# USB_Interface.net
KiCad netlist of a schematic drawn in Altium Designer
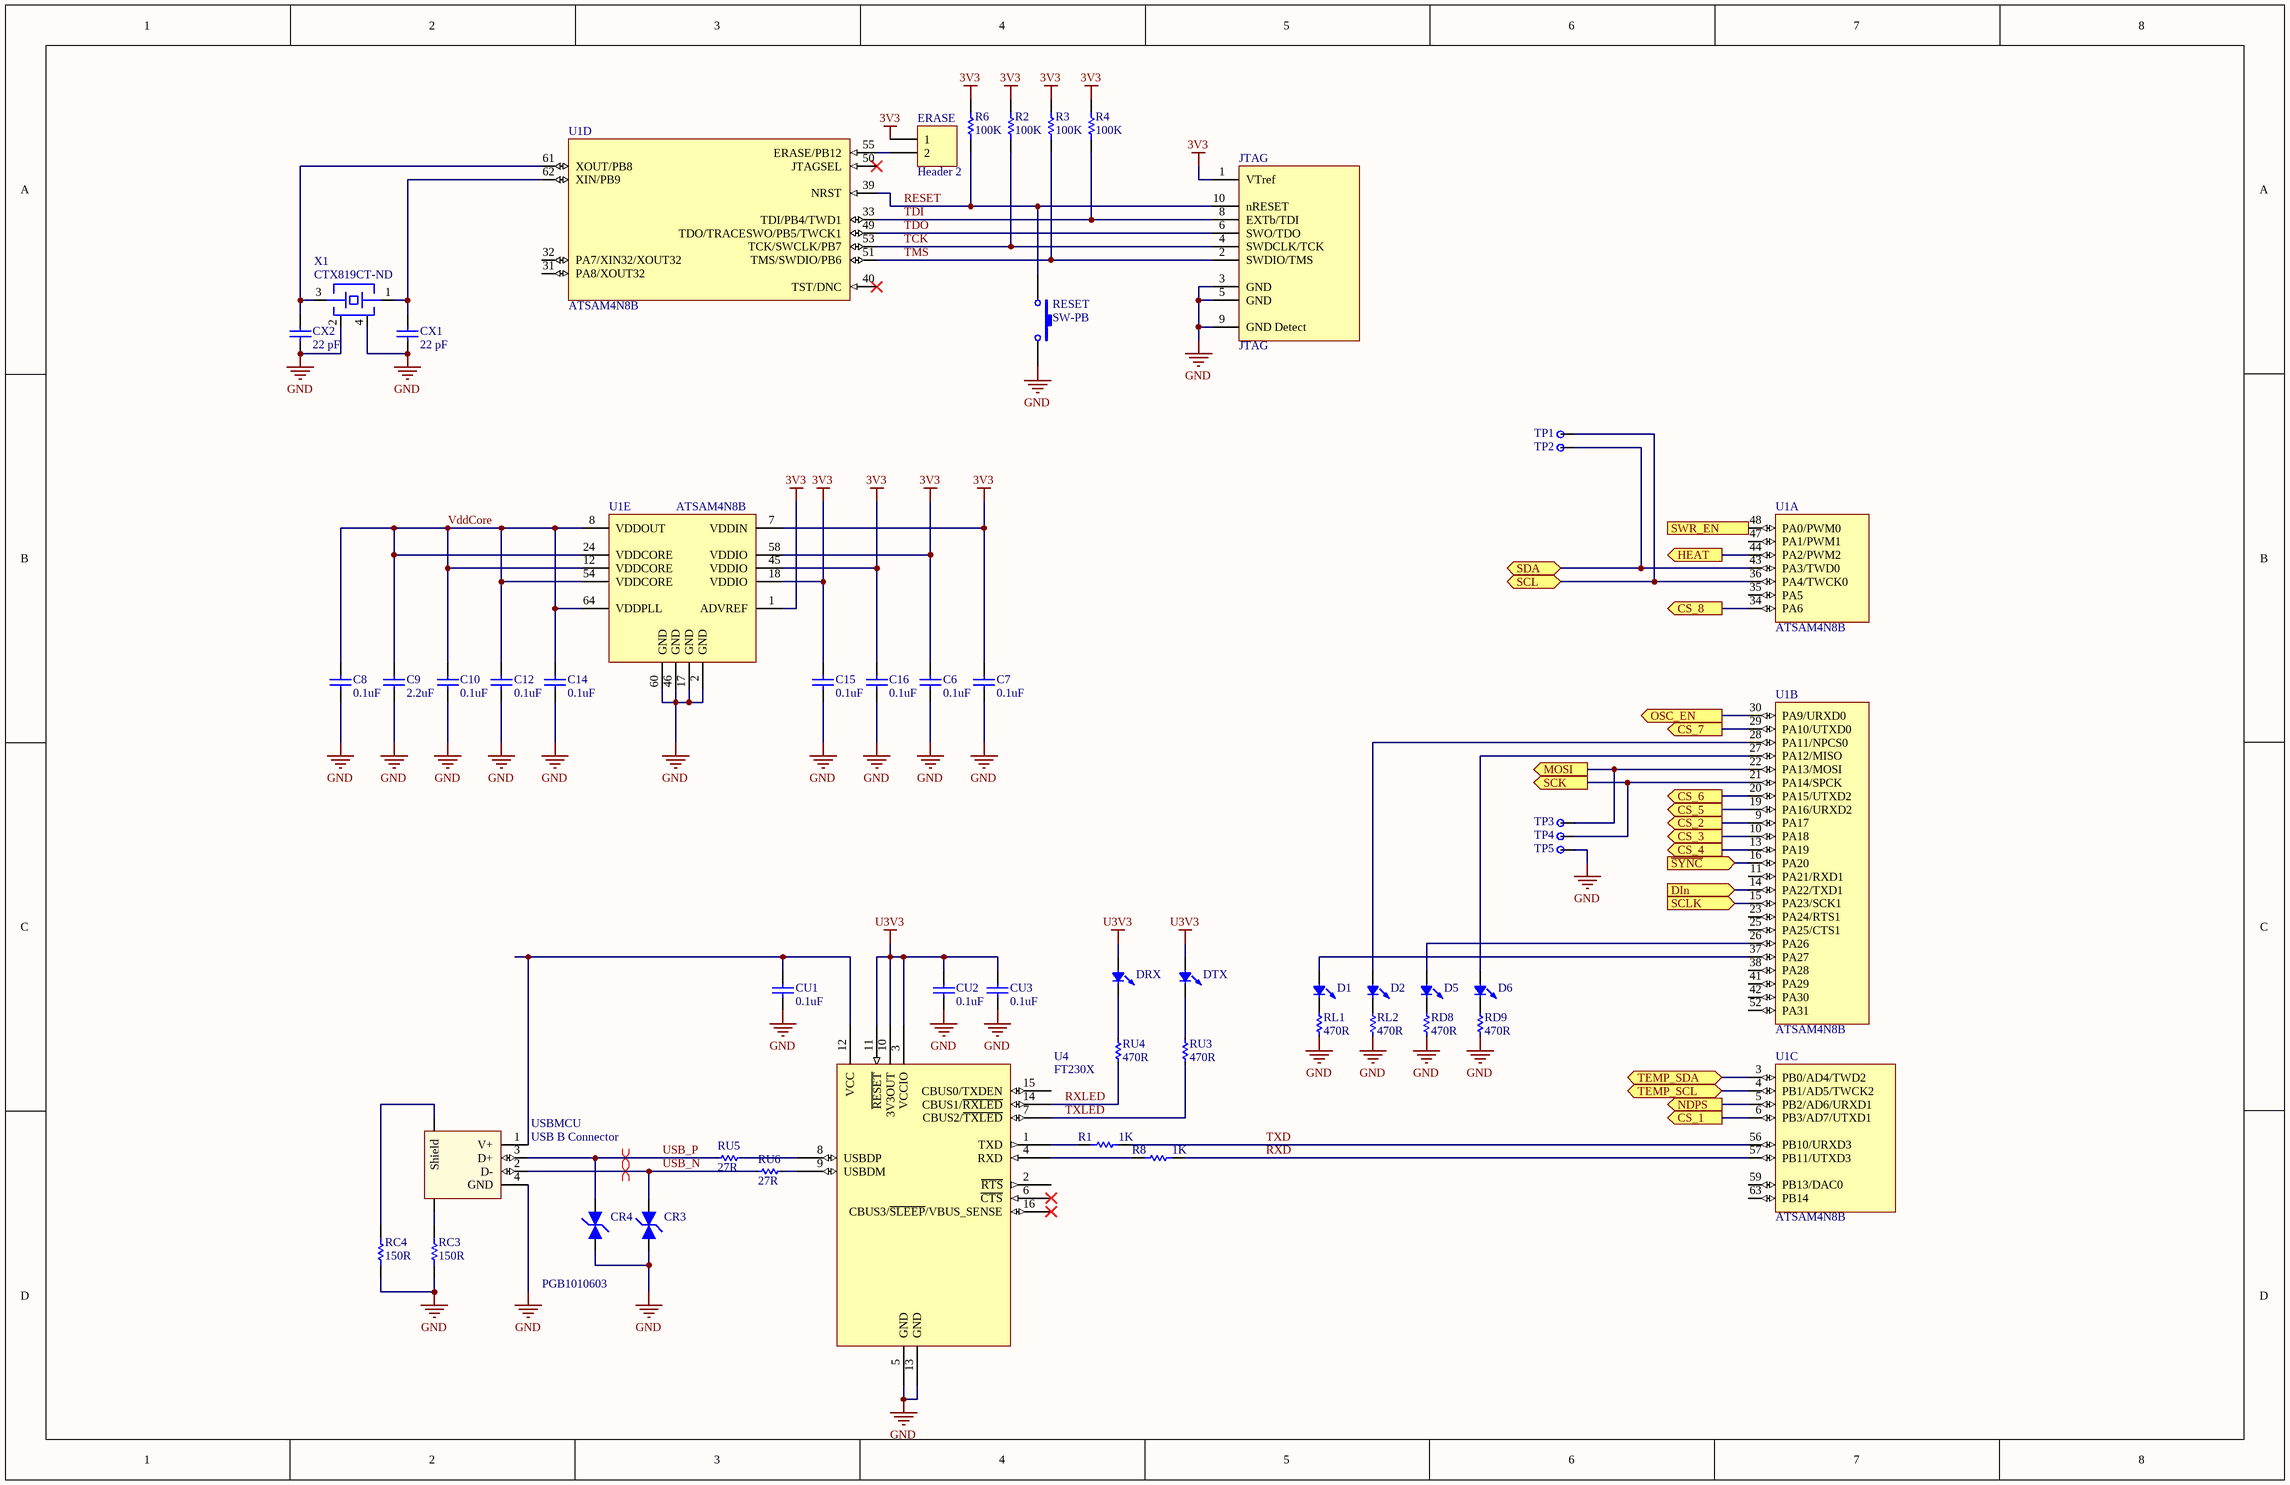
[diagram p0: USB Interface.SchDoc]

(export (version "E")
  (design (tool "Eeschema 10.0.6"))
  (components
    (comp (ref "C6")
      (value "0.1uF")
      (footprint "0603C")
      (description "Capacitor (Semiconductor SIM Model)")
      (fields (field (name "Comment") "Cap Semi") (field (name "PUBLISHER") "Altium Limited"))
      (libsource (lib "Miscellaneous Devices") (part "Cap Semi"))
    )
    (comp (ref "C7")
      (value "0.1uF")
      (footprint "0603C")
      (description "Capacitor (Semiconductor SIM Model)")
      (fields (field (name "Comment") "Cap Semi") (field (name "PUBLISHER") "Altium Limited"))
      (libsource (lib "Miscellaneous Devices") (part "Cap Semi"))
    )
    (comp (ref "C8")
      (value "0.1uF")
      (footprint "0603C")
      (description "Capacitor (Semiconductor SIM Model)")
      (fields (field (name "Comment") "Cap Semi") (field (name "PUBLISHER") "Altium Limited"))
      (libsource (lib "Miscellaneous Devices") (part "Cap Semi"))
    )
    (comp (ref "C9")
      (value "2.2uF")
      (footprint "1206C")
      (description "Capacitor (Semiconductor SIM Model)")
      (fields (field (name "Comment") "Cap Semi") (field (name "PUBLISHER") "Altium Limited"))
      (libsource (lib "Miscellaneous Devices") (part "Cap Semi"))
    )
    (comp (ref "C10")
      (value "0.1uF")
      (footprint "0603C")
      (description "Capacitor (Semiconductor SIM Model)")
      (fields (field (name "Comment") "Cap Semi") (field (name "PUBLISHER") "Altium Limited"))
      (libsource (lib "Miscellaneous Devices") (part "Cap Semi"))
    )
    (comp (ref "C12")
      (value "0.1uF")
      (footprint "0603C")
      (description "Capacitor (Semiconductor SIM Model)")
      (fields (field (name "Comment") "Cap Semi") (field (name "PUBLISHER") "Altium Limited"))
      (libsource (lib "Miscellaneous Devices") (part "Cap Semi"))
    )
    (comp (ref "C14")
      (value "0.1uF")
      (footprint "0603C")
      (description "Capacitor (Semiconductor SIM Model)")
      (fields (field (name "Comment") "Cap Semi") (field (name "PUBLISHER") "Altium Limited"))
      (libsource (lib "Miscellaneous Devices") (part "Cap Semi"))
    )
    (comp (ref "C15")
      (value "0.1uF")
      (footprint "0603C")
      (description "Capacitor (Semiconductor SIM Model)")
      (fields (field (name "Comment") "Cap Semi") (field (name "PUBLISHER") "Altium Limited"))
      (libsource (lib "Miscellaneous Devices") (part "Cap Semi"))
    )
    (comp (ref "C16")
      (value "0.1uF")
      (footprint "0603C")
      (description "Capacitor (Semiconductor SIM Model)")
      (fields (field (name "Comment") "Cap Semi") (field (name "PUBLISHER") "Altium Limited"))
      (libsource (lib "Miscellaneous Devices") (part "Cap Semi"))
    )
    (comp (ref "CR3")
      (value "PGB1010603")
      (footprint "0603PG")
      (description "PulseGuard® Lead-Free 0603 Surface Mount Polymeric ESD Suppressors")
      (libsource (lib "DAQ System") (part "PGB1010603"))
    )
    (comp (ref "CR4")
      (value "PGB1010603")
      (footprint "0603PG")
      (description "PulseGuard® Lead-Free 0603 Surface Mount Polymeric ESD Suppressors")
      (libsource (lib "DAQ System") (part "PGB1010603"))
    )
    (comp (ref "CU1")
      (value "0.1uF")
      (footprint "0603C")
      (description "Capacitor (Semiconductor SIM Model)")
      (fields (field (name "Comment") "Cap Semi") (field (name "PUBLISHER") "Altium Limited"))
      (libsource (lib "Miscellaneous Devices") (part "Cap Semi"))
    )
    (comp (ref "CU2")
      (value "0.1uF")
      (footprint "0603C")
      (description "Capacitor (Semiconductor SIM Model)")
      (fields (field (name "Comment") "Cap Semi") (field (name "PUBLISHER") "Altium Limited"))
      (libsource (lib "Miscellaneous Devices") (part "Cap Semi"))
    )
    (comp (ref "CU3")
      (value "0.1uF")
      (footprint "0603C")
      (description "Capacitor (Semiconductor SIM Model)")
      (fields (field (name "Comment") "Cap Semi") (field (name "PUBLISHER") "Altium Limited"))
      (libsource (lib "Miscellaneous Devices") (part "Cap Semi"))
    )
    (comp (ref "CX1")
      (value "22 pF")
      (footprint "0603C")
      (description "Capacitor (Semiconductor SIM Model)")
      (fields (field (name "Comment") "Cap Semi") (field (name "PUBLISHER") "Altium Limited"))
      (libsource (lib "Miscellaneous Devices") (part "Cap Semi"))
    )
    (comp (ref "CX2")
      (value "22 pF")
      (footprint "0603C")
      (description "Capacitor (Semiconductor SIM Model)")
      (fields (field (name "Comment") "Cap Semi") (field (name "PUBLISHER") "Altium Limited"))
      (libsource (lib "Miscellaneous Devices") (part "Cap Semi"))
    )
    (comp (ref "D1")
      (value "LED0")
      (footprint "0603 SMT LED")
      (description "T 1 3/4 LED")
      (fields (field (name "PUBLISHER") "Altium Limited"))
      (libsource (lib "Miscellaneous Devices") (part "LED0"))
    )
    (comp (ref "D2")
      (value "LED0")
      (footprint "0603 SMT LED")
      (description "T 1 3/4 LED")
      (fields (field (name "PUBLISHER") "Altium Limited"))
      (libsource (lib "Miscellaneous Devices") (part "LED0"))
    )
    (comp (ref "D5")
      (value "LED0")
      (footprint "0603 SMT LED")
      (description "T 1 3/4 LED")
      (fields (field (name "PUBLISHER") "Altium Limited"))
      (libsource (lib "Miscellaneous Devices") (part "LED0"))
    )
    (comp (ref "D6")
      (value "LED0")
      (footprint "0603 SMT LED")
      (description "T 1 3/4 LED")
      (fields (field (name "PUBLISHER") "Altium Limited"))
      (libsource (lib "Miscellaneous Devices") (part "LED0"))
    )
    (comp (ref "DRX")
      (value "LED0")
      (footprint "0603 SMT LED")
      (description "T 1 3/4 LED")
      (fields (field (name "PUBLISHER") "Altium Limited"))
      (libsource (lib "Miscellaneous Devices") (part "LED0"))
    )
    (comp (ref "DTX")
      (value "LED0")
      (footprint "0603 SMT LED")
      (description "T 1 3/4 LED")
      (fields (field (name "PUBLISHER") "Altium Limited"))
      (libsource (lib "Miscellaneous Devices") (part "LED0"))
    )
    (comp (ref "ERASE")
      (value "Header 2")
      (footprint "HDR1X2")
      (description "Header, 2-Pin")
      (fields (field (name "PUBLISHER") "Altium Limited"))
      (libsource (lib "Miscellaneous Connectors") (part "Header 2"))
    )
    (comp (ref "JTAG")
      (value "JTAG")
      (footprint "MHDR2X5 - Shrouded")
      (description "ARM 10-Pin JTAG Interface")
      (libsource (lib "Connectors") (part "ARM JTAG-10"))
    )
    (comp (ref "R1")
      (value "1K")
      (footprint "0603R")
      (description "Semiconductor Resistor")
      (fields (field (name "Comment") "Res Semi") (field (name "PUBLISHER") "Altium Limited"))
      (libsource (lib "Miscellaneous Devices") (part "Res Semi"))
    )
    (comp (ref "R2")
      (value "100K")
      (footprint "0603R")
      (description "Semiconductor Resistor")
      (fields (field (name "Comment") "Res Semi") (field (name "PUBLISHER") "Altium Limited"))
      (libsource (lib "Miscellaneous Devices") (part "Res Semi"))
    )
    (comp (ref "R3")
      (value "100K")
      (footprint "0603R")
      (description "Semiconductor Resistor")
      (fields (field (name "Comment") "Res Semi") (field (name "PUBLISHER") "Altium Limited"))
      (libsource (lib "Miscellaneous Devices") (part "Res Semi"))
    )
    (comp (ref "R4")
      (value "100K")
      (footprint "0603R")
      (description "Semiconductor Resistor")
      (fields (field (name "Comment") "Res Semi") (field (name "PUBLISHER") "Altium Limited"))
      (libsource (lib "Miscellaneous Devices") (part "Res Semi"))
    )
    (comp (ref "R6")
      (value "100K")
      (footprint "0603R")
      (description "Semiconductor Resistor")
      (fields (field (name "Comment") "Res Semi") (field (name "PUBLISHER") "Altium Limited"))
      (libsource (lib "Miscellaneous Devices") (part "Res Semi"))
    )
    (comp (ref "R8")
      (value "1K")
      (footprint "0603R")
      (description "Semiconductor Resistor")
      (fields (field (name "Comment") "Res Semi") (field (name "PUBLISHER") "Altium Limited"))
      (libsource (lib "Miscellaneous Devices") (part "Res Semi"))
    )
    (comp (ref "RC3")
      (value "150R")
      (footprint "1206R")
      (description "Semiconductor Resistor")
      (fields (field (name "Comment") "Res Semi") (field (name "PUBLISHER") "Altium Limited"))
      (libsource (lib "Miscellaneous Devices") (part "Res Semi"))
    )
    (comp (ref "RC4")
      (value "150R")
      (footprint "1206R")
      (description "Semiconductor Resistor")
      (fields (field (name "Comment") "Res Semi") (field (name "PUBLISHER") "Altium Limited"))
      (libsource (lib "Miscellaneous Devices") (part "Res Semi"))
    )
    (comp (ref "RD8")
      (value "470R")
      (footprint "0603R")
      (description "Semiconductor Resistor")
      (fields (field (name "Comment") "Res Semi Small") (field (name "PUBLISHER") "Altium Limited"))
      (libsource (lib "Miscellaneous Devices") (part "Res Semi Small"))
    )
    (comp (ref "RD9")
      (value "470R")
      (footprint "0603R")
      (description "Semiconductor Resistor")
      (fields (field (name "Comment") "Res Semi Small") (field (name "PUBLISHER") "Altium Limited"))
      (libsource (lib "Miscellaneous Devices") (part "Res Semi Small"))
    )
    (comp (ref "RESET")
      (value "SW-PB")
      (footprint "TL3302BF180QG/TR")
      (description "Switch")
      (fields (field (name "PUBLISHER") "Altium Limited"))
      (libsource (lib "Miscellaneous Devices") (part "SW-PB"))
    )
    (comp (ref "RL1")
      (value "470R")
      (footprint "0603R")
      (description "Semiconductor Resistor")
      (fields (field (name "Comment") "Res Semi Small") (field (name "PUBLISHER") "Altium Limited"))
      (libsource (lib "Miscellaneous Devices") (part "Res Semi Small"))
    )
    (comp (ref "RL2")
      (value "470R")
      (footprint "0603R")
      (description "Semiconductor Resistor")
      (fields (field (name "Comment") "Res Semi Small") (field (name "PUBLISHER") "Altium Limited"))
      (libsource (lib "Miscellaneous Devices") (part "Res Semi Small"))
    )
    (comp (ref "RU3")
      (value "470R")
      (footprint "0603R")
      (description "Semiconductor Resistor")
      (fields (field (name "Comment") "Res Semi Small") (field (name "PUBLISHER") "Altium Limited"))
      (libsource (lib "Miscellaneous Devices") (part "Res Semi Small"))
    )
    (comp (ref "RU4")
      (value "470R")
      (footprint "0603R")
      (description "Semiconductor Resistor")
      (fields (field (name "Comment") "Res Semi Small") (field (name "PUBLISHER") "Altium Limited"))
      (libsource (lib "Miscellaneous Devices") (part "Res Semi Small"))
    )
    (comp (ref "RU5")
      (value "27R")
      (footprint "0603R")
      (description "Semiconductor Resistor")
      (fields (field (name "Comment") "Res Semi Small") (field (name "PUBLISHER") "Altium Limited"))
      (libsource (lib "Miscellaneous Devices") (part "Res Semi Small"))
    )
    (comp (ref "RU6")
      (value "27R")
      (footprint "0603R")
      (description "Semiconductor Resistor")
      (fields (field (name "Comment") "Res Semi Small") (field (name "PUBLISHER") "Altium Limited"))
      (libsource (lib "Miscellaneous Devices") (part "Res Semi Small"))
    )
    (comp (ref "TP1")
      (value "Loop Testpoint")
      (footprint "Pad - 70 * 40 mil")
      (libsource (lib "Unsorted") (part "Testpoint"))
    )
    (comp (ref "TP2")
      (value "Loop Testpoint")
      (footprint "Pad - 70 * 40 mil")
      (libsource (lib "Unsorted") (part "Testpoint"))
    )
    (comp (ref "TP3")
      (value "Loop Testpoint")
      (footprint "Pad - 70 * 40 mil")
      (libsource (lib "Unsorted") (part "Testpoint"))
    )
    (comp (ref "TP4")
      (value "Loop Testpoint")
      (footprint "Pad - 70 * 40 mil")
      (libsource (lib "Unsorted") (part "Testpoint"))
    )
    (comp (ref "TP5")
      (value "Loop Testpoint")
      (footprint "Pad - 70 * 40 mil")
      (libsource (lib "Unsorted") (part "Testpoint"))
    )
    (comp (ref "U1")
      (value "ATSAM4N8B")
      (footprint "TSQFP50P1200X1200-64N")
      (description "32 bit Cortex M4 Microcontroller")
      (libsource (lib "ICs") (part "ATSAM4N8B"))
    )
    (comp (ref "U4")
      (value "FT230X")
      (footprint "SOP635P600-16AN")
      (description "USB To Basic Serial Bridge IC")
      (libsource (lib "ICs") (part "FT230X"))
    )
    (comp (ref "USBMCU")
      (value "USB B Connector")
      (footprint "USB Connector (type B)")
      (libsource (lib "DAQ Sstem") (part "USB B connector - Through hole"))
    )
    (comp (ref "X1")
      (value "CTX819CT-ND")
      (footprint "Abracon ABM3B Crystal")
      (description "16 MHz Micro SMT Crystal")
      (libsource (lib "Unsorted") (part "SMT Crystal"))
    )
  )
  (nets
    (net (code "1") (name "/CS_1") (class "Default")
      (node (ref "U1") (pin "6") (pinfunction "PB3/AD7/UTXD1_6") (pintype "bidirectional"))
    )
    (net (code "2") (name "/CS_2") (class "Default")
      (node (ref "U1") (pin "9") (pinfunction "PA17/AD0_9") (pintype "bidirectional"))
    )
    (net (code "3") (name "/CS_3") (class "Default")
      (node (ref "U1") (pin "10") (pinfunction "PA18/AD1_10") (pintype "bidirectional"))
    )
    (net (code "4") (name "/CS_4") (class "Default")
      (node (ref "U1") (pin "13") (pinfunction "PA19/AD2_13") (pintype "bidirectional"))
    )
    (net (code "5") (name "/CS_5") (class "Default")
      (node (ref "U1") (pin "19") (pinfunction "PA16/URXD2_19") (pintype "bidirectional"))
    )
    (net (code "6") (name "/CS_6") (class "Default")
      (node (ref "U1") (pin "20") (pinfunction "PA15/UTXD2_20") (pintype "bidirectional"))
    )
    (net (code "7") (name "/CS_7") (class "Default")
      (node (ref "U1") (pin "29") (pinfunction "PA10/UTXD0_29") (pintype "bidirectional"))
    )
    (net (code "8") (name "/CS_8") (class "Default")
      (node (ref "U1") (pin "34") (pinfunction "PA6_34") (pintype "bidirectional"))
    )
    (net (code "9") (name "/DIn") (class "Default")
      (node (ref "U1") (pin "14") (pinfunction "PA22/AD9_14") (pintype "bidirectional"))
    )
    (net (code "10") (name "/HEAT") (class "Default")
      (node (ref "U1") (pin "44") (pinfunction "PA2/PWM2_44") (pintype "bidirectional"))
    )
    (net (code "11") (name "/MOSI") (class "Default")
      (node (ref "TP3") (pin "1") (pinfunction "1_1") (pintype "passive"))
      (node (ref "U1") (pin "22") (pinfunction "PA13/MOSI_22") (pintype "bidirectional"))
    )
    (net (code "12") (name "/NDPS") (class "Default")
      (node (ref "U1") (pin "5") (pinfunction "PB2/AD6/URXD1_5") (pintype "bidirectional"))
    )
    (net (code "13") (name "/OSC_EN") (class "Default")
      (node (ref "U1") (pin "30") (pinfunction "PA9/URXD0_30") (pintype "bidirectional"))
    )
    (net (code "14") (name "/RESET") (class "Default")
      (node (ref "JTAG") (pin "10") (pinfunction "nRESET_10") (pintype "passive"))
      (node (ref "R6") (pin "1") (pinfunction "1_1") (pintype "passive"))
      (node (ref "RESET") (pin "1") (pinfunction "1_1") (pintype "passive"))
      (node (ref "U1") (pin "39") (pinfunction "NRST_39") (pintype "input"))
    )
    (net (code "15") (name "/RXD") (class "Default")
      (node (ref "R8") (pin "2") (pinfunction "2_2") (pintype "passive"))
      (node (ref "U1") (pin "57") (pinfunction "PB11/UTXD3_57") (pintype "bidirectional"))
    )
    (net (code "16") (name "/RXLED") (class "Default")
      (node (ref "RU4") (pin "2") (pinfunction "2_2") (pintype "passive"))
      (node (ref "U4") (pin "14") (pinfunction "CBUS1/~{RXLED}_14") (pintype "bidirectional"))
    )
    (net (code "17") (name "/SCK") (class "Default")
      (node (ref "TP4") (pin "1") (pinfunction "1_1") (pintype "passive"))
      (node (ref "U1") (pin "21") (pinfunction "PA14/SPCK_21") (pintype "bidirectional"))
    )
    (net (code "18") (name "/SCL") (class "Default")
      (node (ref "TP1") (pin "1") (pinfunction "1_1") (pintype "passive"))
      (node (ref "U1") (pin "36") (pinfunction "PA4/TWCK0_36") (pintype "bidirectional"))
    )
    (net (code "19") (name "/SCLK") (class "Default")
      (node (ref "U1") (pin "15") (pinfunction "PA23_15") (pintype "bidirectional"))
    )
    (net (code "20") (name "/SDA") (class "Default")
      (node (ref "TP2") (pin "1") (pinfunction "1_1") (pintype "passive"))
      (node (ref "U1") (pin "43") (pinfunction "PA3/TWD0_43") (pintype "bidirectional"))
    )
    (net (code "21") (name "/SWR_EN") (class "Default")
      (node (ref "U1") (pin "48") (pinfunction "PA0/PWM0_48") (pintype "bidirectional"))
    )
    (net (code "22") (name "/SYNC") (class "Default")
      (node (ref "U1") (pin "16") (pinfunction "PA20/AD3_16") (pintype "bidirectional"))
    )
    (net (code "23") (name "/TCK") (class "Default")
      (node (ref "JTAG") (pin "4") (pinfunction "SWDCLK/TCK_4") (pintype "passive"))
      (node (ref "R2") (pin "1") (pinfunction "1_1") (pintype "passive"))
      (node (ref "U1") (pin "53") (pinfunction "TCK/SWCLK/PB7_53") (pintype "bidirectional"))
    )
    (net (code "24") (name "/TDI") (class "Default")
      (node (ref "JTAG") (pin "8") (pinfunction "EXTb/TDI_8") (pintype "passive"))
      (node (ref "R4") (pin "1") (pinfunction "1_1") (pintype "passive"))
      (node (ref "U1") (pin "33") (pinfunction "TDI/PB4/TWD1_33") (pintype "bidirectional"))
    )
    (net (code "25") (name "/TDO") (class "Default")
      (node (ref "JTAG") (pin "6") (pinfunction "SWO/TDO_6") (pintype "passive"))
      (node (ref "U1") (pin "49") (pinfunction "TDO/TRACESWO/PB5/TWCK1_49") (pintype "bidirectional"))
    )
    (net (code "26") (name "/TEMP_SCL") (class "Default")
      (node (ref "U1") (pin "4") (pinfunction "PB1/AD5/TWCK2_4") (pintype "bidirectional"))
    )
    (net (code "27") (name "/TEMP_SDA") (class "Default")
      (node (ref "U1") (pin "3") (pinfunction "PB0/AD4/TWD2_3") (pintype "bidirectional"))
    )
    (net (code "28") (name "/TMS") (class "Default")
      (node (ref "JTAG") (pin "2") (pinfunction "SWDIO/TMS_2") (pintype "passive"))
      (node (ref "R3") (pin "1") (pinfunction "1_1") (pintype "passive"))
      (node (ref "U1") (pin "51") (pinfunction "TMS/SWDIO/PB6_51") (pintype "bidirectional"))
    )
    (net (code "29") (name "/TXD") (class "Default")
      (node (ref "R1") (pin "2") (pinfunction "2_2") (pintype "passive"))
      (node (ref "U1") (pin "56") (pinfunction "PB10/URXD3_56") (pintype "bidirectional"))
    )
    (net (code "30") (name "/TXLED") (class "Default")
      (node (ref "RU3") (pin "2") (pinfunction "2_2") (pintype "passive"))
      (node (ref "U4") (pin "7") (pinfunction "CBUS2/~{TXLED}_7") (pintype "bidirectional"))
    )
    (net (code "31") (name "/USB_N") (class "Default")
      (node (ref "CR3") (pin "1") (pinfunction "1_1") (pintype "passive"))
      (node (ref "RU6") (pin "1") (pinfunction "1_1") (pintype "passive"))
      (node (ref "USBMCU") (pin "2") (pinfunction "D-_2") (pintype "bidirectional"))
    )
    (net (code "32") (name "/USB_P") (class "Default")
      (node (ref "CR4") (pin "1") (pinfunction "1_1") (pintype "passive"))
      (node (ref "RU5") (pin "1") (pinfunction "1_1") (pintype "passive"))
      (node (ref "USBMCU") (pin "3") (pinfunction "D+_3") (pintype "bidirectional"))
    )
    (net (code "33") (name "/VddCore") (class "Default")
      (node (ref "C10") (pin "2") (pinfunction "2_2") (pintype "passive"))
      (node (ref "C12") (pin "2") (pinfunction "2_2") (pintype "passive"))
      (node (ref "C14") (pin "2") (pinfunction "2_2") (pintype "passive"))
      (node (ref "C8") (pin "2") (pinfunction "2_2") (pintype "passive"))
      (node (ref "C9") (pin "2") (pinfunction "2_2") (pintype "passive"))
      (node (ref "U1") (pin "12") (pinfunction "VDDCORE_12") (pintype "power_in"))
      (node (ref "U1") (pin "24") (pinfunction "VDDCORE_24") (pintype "power_in"))
      (node (ref "U1") (pin "54") (pinfunction "VDDCORE_54") (pintype "power_in"))
      (node (ref "U1") (pin "64") (pinfunction "VDDPLL_64") (pintype "power_in"))
      (node (ref "U1") (pin "8") (pinfunction "VDDOUT_8") (pintype "power_in"))
    )
    (net (code "34") (name "3V3") (class "Default")
      (node (ref "C15") (pin "2") (pinfunction "2_2") (pintype "passive"))
      (node (ref "C16") (pin "2") (pinfunction "2_2") (pintype "passive"))
      (node (ref "C6") (pin "2") (pinfunction "2_2") (pintype "passive"))
      (node (ref "C7") (pin "2") (pinfunction "2_2") (pintype "passive"))
      (node (ref "ERASE") (pin "1") (pinfunction "1_1") (pintype "passive"))
      (node (ref "JTAG") (pin "1") (pinfunction "VTref_1") (pintype "passive"))
      (node (ref "R2") (pin "2") (pinfunction "2_2") (pintype "passive"))
      (node (ref "R3") (pin "2") (pinfunction "2_2") (pintype "passive"))
      (node (ref "R4") (pin "2") (pinfunction "2_2") (pintype "passive"))
      (node (ref "R6") (pin "2") (pinfunction "2_2") (pintype "passive"))
      (node (ref "U1") (pin "1") (pinfunction "ADVREF_1") (pintype "power_in"))
      (node (ref "U1") (pin "18") (pinfunction "VDDIO_18") (pintype "power_in"))
      (node (ref "U1") (pin "45") (pinfunction "VDDIO_45") (pintype "power_in"))
      (node (ref "U1") (pin "58") (pinfunction "VDDIO_58") (pintype "power_in"))
      (node (ref "U1") (pin "7") (pinfunction "VDDIN_7") (pintype "power_in"))
    )
    (net (code "35") (name "GND") (class "Default")
      (node (ref "C10") (pin "1") (pinfunction "1_1") (pintype "passive"))
      (node (ref "C12") (pin "1") (pinfunction "1_1") (pintype "passive"))
      (node (ref "C14") (pin "1") (pinfunction "1_1") (pintype "passive"))
      (node (ref "C15") (pin "1") (pinfunction "1_1") (pintype "passive"))
      (node (ref "C16") (pin "1") (pinfunction "1_1") (pintype "passive"))
      (node (ref "C6") (pin "1") (pinfunction "1_1") (pintype "passive"))
      (node (ref "C7") (pin "1") (pinfunction "1_1") (pintype "passive"))
      (node (ref "C8") (pin "1") (pinfunction "1_1") (pintype "passive"))
      (node (ref "C9") (pin "1") (pinfunction "1_1") (pintype "passive"))
      (node (ref "CR3") (pin "2") (pinfunction "2_2") (pintype "passive"))
      (node (ref "CR4") (pin "2") (pinfunction "2_2") (pintype "passive"))
      (node (ref "CU1") (pin "1") (pinfunction "1_1") (pintype "passive"))
      (node (ref "CU2") (pin "1") (pinfunction "1_1") (pintype "passive"))
      (node (ref "CU3") (pin "1") (pinfunction "1_1") (pintype "passive"))
      (node (ref "CX1") (pin "1") (pinfunction "1_1") (pintype "passive"))
      (node (ref "CX2") (pin "1") (pinfunction "1_1") (pintype "passive"))
      (node (ref "JTAG") (pin "3") (pinfunction "GND_3") (pintype "power_in"))
      (node (ref "JTAG") (pin "5") (pinfunction "GND_5") (pintype "power_in"))
      (node (ref "JTAG") (pin "9") (pinfunction "GND_Detect_9") (pintype "passive"))
      (node (ref "RC3") (pin "1") (pinfunction "1_1") (pintype "passive"))
      (node (ref "RC4") (pin "1") (pinfunction "1_1") (pintype "passive"))
      (node (ref "RD8") (pin "2") (pinfunction "2_2") (pintype "passive"))
      (node (ref "RD9") (pin "2") (pinfunction "2_2") (pintype "passive"))
      (node (ref "RESET") (pin "2") (pinfunction "2_2") (pintype "passive"))
      (node (ref "RL1") (pin "2") (pinfunction "2_2") (pintype "passive"))
      (node (ref "RL2") (pin "2") (pinfunction "2_2") (pintype "passive"))
      (node (ref "TP5") (pin "1") (pinfunction "1_1") (pintype "passive"))
      (node (ref "U1") (pin "17") (pinfunction "GND_17") (pintype "power_in"))
      (node (ref "U1") (pin "2") (pinfunction "GND_2") (pintype "power_in"))
      (node (ref "U1") (pin "46") (pinfunction "GND_46") (pintype "power_in"))
      (node (ref "U1") (pin "60") (pinfunction "GND_60") (pintype "power_in"))
      (node (ref "U4") (pin "13") (pinfunction "GND_13") (pintype "power_in"))
      (node (ref "U4") (pin "5") (pinfunction "GND_5") (pintype "power_in"))
      (node (ref "USBMCU") (pin "4") (pinfunction "GND_4") (pintype "power_in"))
      (node (ref "X1") (pin "2") (pinfunction "2_2") (pintype "passive"))
      (node (ref "X1") (pin "4") (pinfunction "4_4") (pintype "passive"))
    )
    (net (code "36") (name "Net-(D1-Pad2)") (class "Default")
      (node (ref "D1") (pin "2") (pinfunction "2_2") (pintype "passive"))
      (node (ref "RL1") (pin "1") (pinfunction "1_1") (pintype "passive"))
    )
    (net (code "37") (name "Net-(D2-Pad2)") (class "Default")
      (node (ref "D2") (pin "2") (pinfunction "2_2") (pintype "passive"))
      (node (ref "RL2") (pin "1") (pinfunction "1_1") (pintype "passive"))
    )
    (net (code "38") (name "Net-(D5-Pad2)") (class "Default")
      (node (ref "D5") (pin "2") (pinfunction "2_2") (pintype "passive"))
      (node (ref "RD8") (pin "1") (pinfunction "1_1") (pintype "passive"))
    )
    (net (code "39") (name "Net-(D6-Pad2)") (class "Default")
      (node (ref "D6") (pin "2") (pinfunction "2_2") (pintype "passive"))
      (node (ref "RD9") (pin "1") (pinfunction "1_1") (pintype "passive"))
    )
    (net (code "40") (name "Net-(DRX-Pad2)") (class "Default")
      (node (ref "DRX") (pin "2") (pinfunction "2_2") (pintype "passive"))
      (node (ref "RU4") (pin "1") (pinfunction "1_1") (pintype "passive"))
    )
    (net (code "41") (name "Net-(DTX-Pad2)") (class "Default")
      (node (ref "DTX") (pin "2") (pinfunction "2_2") (pintype "passive"))
      (node (ref "RU3") (pin "1") (pinfunction "1_1") (pintype "passive"))
    )
    (net (code "42") (name "Net-(U1B-PA11{slash}NPCS0)") (class "Default")
      (node (ref "D2") (pin "1") (pinfunction "1_1") (pintype "passive"))
      (node (ref "U1") (pin "28") (pinfunction "PA11/NPCS0_28") (pintype "bidirectional"))
    )
    (net (code "43") (name "Net-(U1B-PA12{slash}MISO)") (class "Default")
      (node (ref "D6") (pin "1") (pinfunction "1_1") (pintype "passive"))
      (node (ref "U1") (pin "27") (pinfunction "PA12/MISO_27") (pintype "bidirectional"))
    )
    (net (code "44") (name "Net-(U1B-PA26)") (class "Default")
      (node (ref "D5") (pin "1") (pinfunction "1_1") (pintype "passive"))
      (node (ref "U1") (pin "26") (pinfunction "PA26_26") (pintype "bidirectional"))
    )
    (net (code "45") (name "Net-(U1B-PA27)") (class "Default")
      (node (ref "D1") (pin "1") (pinfunction "1_1") (pintype "passive"))
      (node (ref "U1") (pin "37") (pinfunction "PA27_37") (pintype "bidirectional"))
    )
    (net (code "46") (name "Net-(U1D-ERASE{slash}PB12)") (class "Default")
      (node (ref "ERASE") (pin "2") (pinfunction "2_2") (pintype "passive"))
      (node (ref "U1") (pin "55") (pinfunction "ERASE/PB12_55") (pintype "input"))
    )
    (net (code "47") (name "Net-(U1D-XIN{slash}PB9)") (class "Default")
      (node (ref "CX1") (pin "2") (pinfunction "2_2") (pintype "passive"))
      (node (ref "U1") (pin "62") (pinfunction "XIN/PB9_62") (pintype "bidirectional"))
      (node (ref "X1") (pin "1") (pinfunction "1_1") (pintype "passive"))
    )
    (net (code "48") (name "Net-(U1D-XOUT{slash}PB8)") (class "Default")
      (node (ref "CX2") (pin "2") (pinfunction "2_2") (pintype "passive"))
      (node (ref "U1") (pin "61") (pinfunction "XOUT/PB8_61") (pintype "bidirectional"))
      (node (ref "X1") (pin "3") (pinfunction "3_3") (pintype "passive"))
    )
    (net (code "49") (name "Net-(U4-RXD)") (class "Default")
      (node (ref "R8") (pin "1") (pinfunction "1_1") (pintype "passive"))
      (node (ref "U4") (pin "4") (pinfunction "RXD_4") (pintype "input"))
    )
    (net (code "50") (name "Net-(U4-TXD)") (class "Default")
      (node (ref "R1") (pin "1") (pinfunction "1_1") (pintype "passive"))
      (node (ref "U4") (pin "1") (pinfunction "TXD_1") (pintype "output"))
    )
    (net (code "51") (name "Net-(U4-USBDM)") (class "Default")
      (node (ref "RU6") (pin "2") (pinfunction "2_2") (pintype "passive"))
      (node (ref "U4") (pin "9") (pinfunction "USBDM_9") (pintype "bidirectional"))
    )
    (net (code "52") (name "Net-(U4-USBDP)") (class "Default")
      (node (ref "RU5") (pin "2") (pinfunction "2_2") (pintype "passive"))
      (node (ref "U4") (pin "8") (pinfunction "USBDP_8") (pintype "bidirectional"))
    )
    (net (code "53") (name "Net-(U4-VCC)") (class "Default")
      (node (ref "CU1") (pin "2") (pinfunction "2_2") (pintype "passive"))
      (node (ref "U4") (pin "12") (pinfunction "VCC_12") (pintype "power_in"))
      (node (ref "USBMCU") (pin "1") (pinfunction "V+_1") (pintype "power_in"))
    )
    (net (code "54") (name "Net-(USBMCU-Gnd)") (class "Default")
      (node (ref "RC3") (pin "2") (pinfunction "2_2") (pintype "passive"))
      (node (ref "USBMCU") (pin "5") (pinfunction "Gnd_5") (pintype "passive"))
    )
    (net (code "55") (name "Net-(USBMCU-Shield)") (class "Default")
      (node (ref "RC4") (pin "2") (pinfunction "2_2") (pintype "passive"))
      (node (ref "USBMCU") (pin "6") (pinfunction "Shield_6") (pintype "passive"))
    )
    (net (code "56") (name "U3V3") (class "Default")
      (node (ref "CU2") (pin "2") (pinfunction "2_2") (pintype "passive"))
      (node (ref "CU3") (pin "2") (pinfunction "2_2") (pintype "passive"))
      (node (ref "DRX") (pin "1") (pinfunction "1_1") (pintype "passive"))
      (node (ref "DTX") (pin "1") (pinfunction "1_1") (pintype "passive"))
      (node (ref "U4") (pin "10") (pinfunction "3V3OUT_10") (pintype "power_in"))
      (node (ref "U4") (pin "11") (pinfunction "~{RESET}_11") (pintype "input"))
      (node (ref "U4") (pin "3") (pinfunction "VCCIO_3") (pintype "power_in"))
    )
    (net (code "57") (name "unconnected-(U1A-PA1{slash}PWM1-Pad47)") (class "Default")
      (node (ref "U1") (pin "47") (pinfunction "PA1/PWM1_47") (pintype "bidirectional"))
    )
    (net (code "58") (name "unconnected-(U1A-PA5-Pad35)") (class "Default")
      (node (ref "U1") (pin "35") (pinfunction "PA5_35") (pintype "bidirectional"))
    )
    (net (code "59") (name "unconnected-(U1B-PA21{slash}AD8-Pad11)") (class "Default")
      (node (ref "U1") (pin "11") (pinfunction "PA21/AD8_11") (pintype "bidirectional"))
    )
    (net (code "60") (name "unconnected-(U1B-PA24-Pad23)") (class "Default")
      (node (ref "U1") (pin "23") (pinfunction "PA24_23") (pintype "bidirectional"))
    )
    (net (code "61") (name "unconnected-(U1B-PA25-Pad25)") (class "Default")
      (node (ref "U1") (pin "25") (pinfunction "PA25_25") (pintype "bidirectional"))
    )
    (net (code "62") (name "unconnected-(U1B-PA28-Pad38)") (class "Default")
      (node (ref "U1") (pin "38") (pinfunction "PA28_38") (pintype "bidirectional"))
    )
    (net (code "63") (name "unconnected-(U1B-PA29-Pad41)") (class "Default")
      (node (ref "U1") (pin "41") (pinfunction "PA29_41") (pintype "bidirectional"))
    )
    (net (code "64") (name "unconnected-(U1B-PA30-Pad42)") (class "Default")
      (node (ref "U1") (pin "42") (pinfunction "PA30_42") (pintype "bidirectional"))
    )
    (net (code "65") (name "unconnected-(U1B-PA31-Pad52)") (class "Default")
      (node (ref "U1") (pin "52") (pinfunction "PA31_52") (pintype "bidirectional"))
    )
    (net (code "66") (name "unconnected-(U1C-PB13{slash}DAC0-Pad59)") (class "Default")
      (node (ref "U1") (pin "59") (pinfunction "PB13/DAC0_59") (pintype "bidirectional"))
    )
    (net (code "67") (name "unconnected-(U1C-PB14-Pad63)") (class "Default")
      (node (ref "U1") (pin "63") (pinfunction "PB14_63") (pintype "bidirectional"))
    )
    (net (code "68") (name "unconnected-(U1D-JTAGSEL-Pad50)") (class "Default")
      (node (ref "U1") (pin "50") (pinfunction "JTAGSEL_50") (pintype "input+no_connect"))
    )
    (net (code "69") (name "unconnected-(U1D-PA7{slash}XIN32{slash}XOUT32-Pad32)") (class "Default")
      (node (ref "U1") (pin "32") (pinfunction "PA7/XIN32/XOUT32_32") (pintype "bidirectional"))
    )
    (net (code "70") (name "unconnected-(U1D-PA8{slash}XOUT32-Pad31)") (class "Default")
      (node (ref "U1") (pin "31") (pinfunction "PA8/XOUT32_31") (pintype "bidirectional"))
    )
    (net (code "71") (name "unconnected-(U1D-TST{slash}DNC-Pad40)") (class "Default")
      (node (ref "U1") (pin "40") (pinfunction "TST/DNC_40") (pintype "input+no_connect"))
    )
    (net (code "72") (name "unconnected-(U4-CBUS0{slash}TXDEN-Pad15)") (class "Default")
      (node (ref "U4") (pin "15") (pinfunction "CBUS0/TXDEN_15") (pintype "bidirectional"))
    )
    (net (code "73") (name "unconnected-(U4-CBUS3{slash}~{SLEEP}{slash}VBUS_SENSE-Pad16)") (class "Default")
      (node (ref "U4") (pin "16") (pinfunction "CBUS3/~{SLEEP}/VBUS_SENSE_16") (pintype "bidirectional+no_connect"))
    )
    (net (code "74") (name "unconnected-(U4-CTS-Pad6)") (class "Default")
      (node (ref "U4") (pin "6") (pinfunction "CTS_6") (pintype "input+no_connect"))
    )
    (net (code "75") (name "unconnected-(U4-NC-Pad8)") (class "Default")
      (node (ref "U4") (pin "8") (pinfunction "NC_8") (pintype "passive"))
    )
    (net (code "76") (name "unconnected-(U4-NC-Pad24)") (class "Default")
      (node (ref "U4") (pin "24") (pinfunction "NC_24") (pintype "passive"))
    )
    (net (code "77") (name "unconnected-(U4-RTS-Pad2)") (class "Default")
      (node (ref "U4") (pin "2") (pinfunction "RTS_2") (pintype "output"))
    )
  )
)
